# LoginNFC.net
KiCad netlist of a schematic drawn in EAGLE
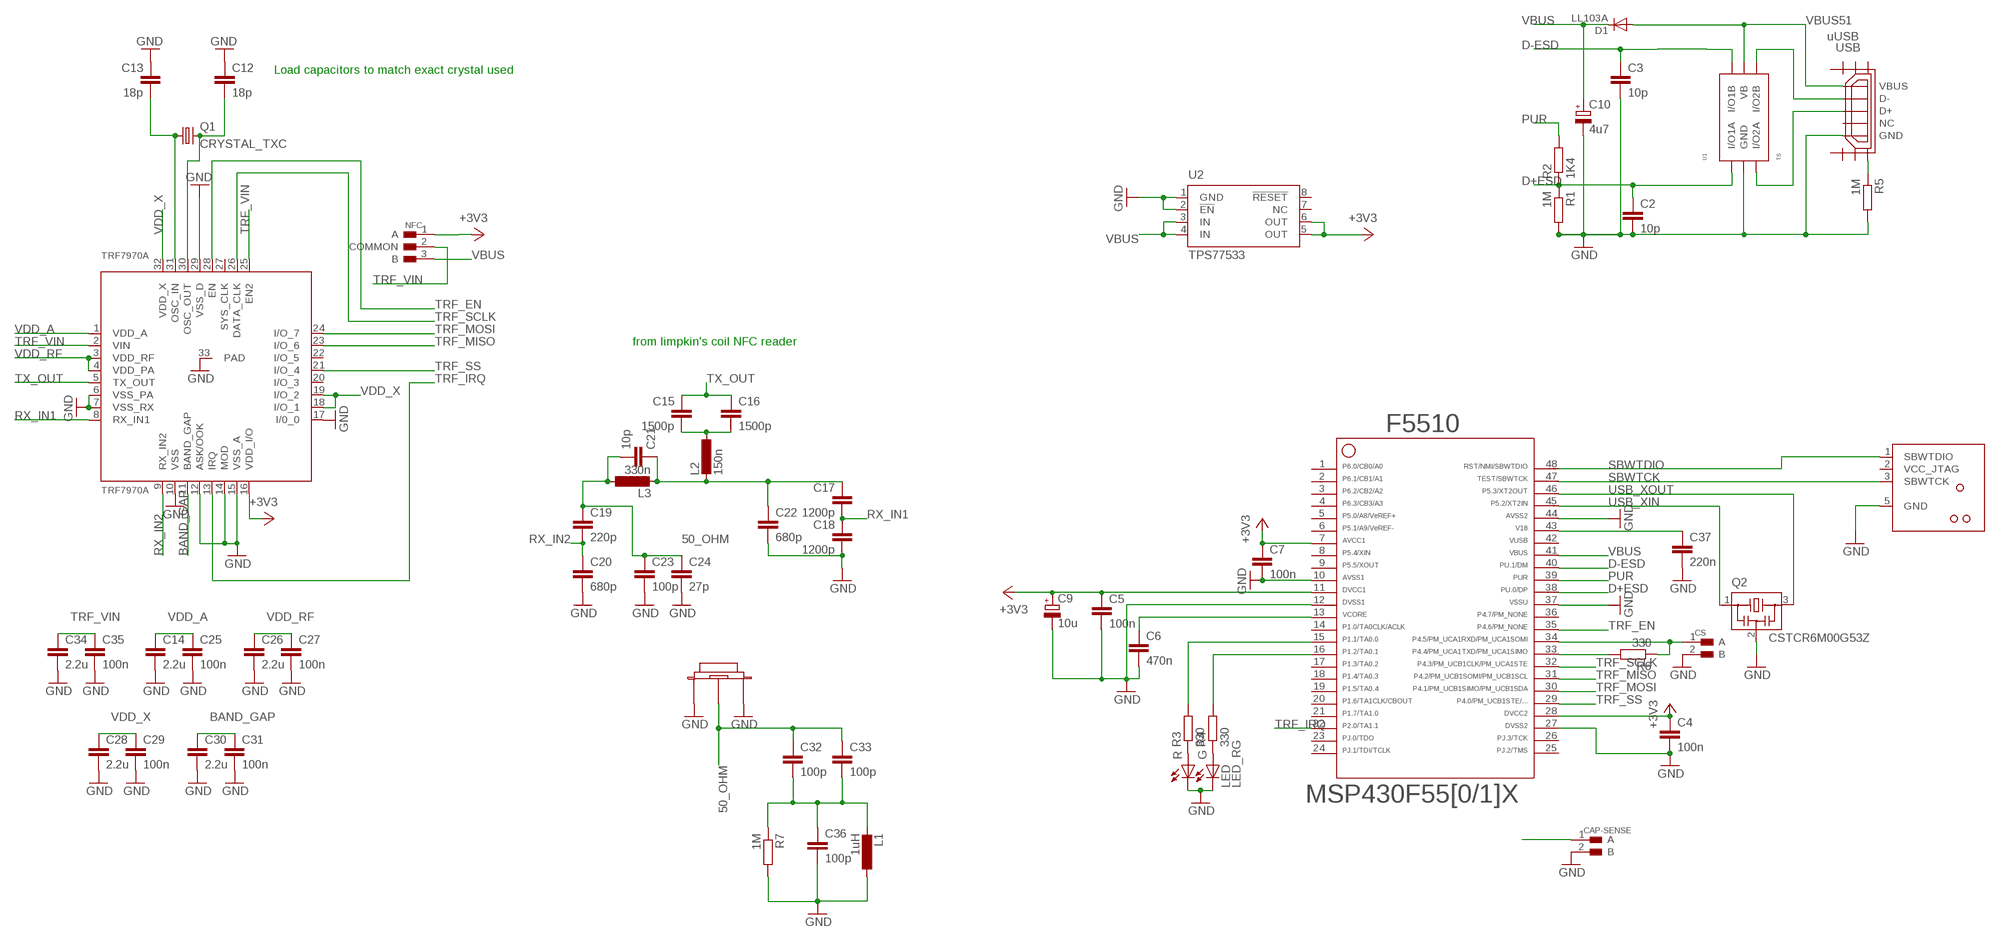
[diagram p0: schematic, sheet 1]

(export (version "E")
  (design (tool "Eeschema 10.0.6"))
  (components
    (comp (ref "C2")
      (value "10p")
      (footprint "eagle-import:C0805")
      (libsource (lib "eagle-import") (part "C-EUC0805"))
    )
    (comp (ref "C3")
      (value "10p")
      (footprint "eagle-import:C0805")
      (libsource (lib "eagle-import") (part "C-EUC0805"))
    )
    (comp (ref "C4")
      (value "100n")
      (footprint "eagle-import:C0805")
      (libsource (lib "eagle-import") (part "C-EUC0805"))
    )
    (comp (ref "C5")
      (value "100n")
      (footprint "eagle-import:C0805")
      (libsource (lib "eagle-import") (part "C-EUC0805"))
    )
    (comp (ref "C6")
      (value "470n")
      (footprint "eagle-import:C0805")
      (libsource (lib "eagle-import") (part "C-EUC0805"))
    )
    (comp (ref "C7")
      (value "100n")
      (footprint "eagle-import:C0805")
      (libsource (lib "eagle-import") (part "C-EUC0805"))
    )
    (comp (ref "C9")
      (value "10u")
      (footprint "eagle-import:A_3216-18R")
      (libsource (lib "eagle-import") (part "CPOL-EUA/3216-18R"))
    )
    (comp (ref "C10")
      (value "4u7")
      (footprint "eagle-import:A_3216-18R")
      (libsource (lib "eagle-import") (part "CPOL-EUA/3216-18R"))
    )
    (comp (ref "C12")
      (value "18p")
      (footprint "eagle-import:C0805")
      (libsource (lib "eagle-import") (part "C-EU_C0805"))
    )
    (comp (ref "C13")
      (value "18p")
      (footprint "eagle-import:C0805")
      (libsource (lib "eagle-import") (part "C-EU_C0805"))
    )
    (comp (ref "C14")
      (value "2.2u")
      (footprint "eagle-import:C0805")
      (libsource (lib "eagle-import") (part "C-EU_C0805"))
    )
    (comp (ref "C15")
      (value "1500p")
      (footprint "eagle-import:C0805")
      (libsource (lib "eagle-import") (part "C-EUC0805"))
    )
    (comp (ref "C16")
      (value "1500p")
      (footprint "eagle-import:C0805")
      (libsource (lib "eagle-import") (part "C-EUC0805"))
    )
    (comp (ref "C17")
      (value "1200p")
      (footprint "eagle-import:C0805")
      (libsource (lib "eagle-import") (part "C-EUC0805"))
    )
    (comp (ref "C18")
      (value "1200p")
      (footprint "eagle-import:C0805")
      (libsource (lib "eagle-import") (part "C-EUC0805"))
    )
    (comp (ref "C19")
      (value "220p")
      (footprint "eagle-import:C0805")
      (libsource (lib "eagle-import") (part "C-EUC0805"))
    )
    (comp (ref "C20")
      (value "680p")
      (footprint "eagle-import:C0805")
      (libsource (lib "eagle-import") (part "C-EUC0805"))
    )
    (comp (ref "C21")
      (value "10p")
      (footprint "eagle-import:C0805")
      (libsource (lib "eagle-import") (part "C-EUC0805"))
    )
    (comp (ref "C22")
      (value "680p")
      (footprint "eagle-import:C0805")
      (libsource (lib "eagle-import") (part "C-EUC0805"))
    )
    (comp (ref "C23")
      (value "100p")
      (footprint "eagle-import:C0805")
      (libsource (lib "eagle-import") (part "C-EUC0805"))
    )
    (comp (ref "C24")
      (value "27p")
      (footprint "eagle-import:C0805")
      (libsource (lib "eagle-import") (part "C-EUC0805"))
    )
    (comp (ref "C25")
      (value "100n")
      (footprint "eagle-import:C0805")
      (libsource (lib "eagle-import") (part "C-EU_C0805"))
    )
    (comp (ref "C26")
      (value "2.2u")
      (footprint "eagle-import:C0805")
      (libsource (lib "eagle-import") (part "C-EU_C0805"))
    )
    (comp (ref "C27")
      (value "100n")
      (footprint "eagle-import:C0805")
      (libsource (lib "eagle-import") (part "C-EU_C0805"))
    )
    (comp (ref "C28")
      (value "2.2u")
      (footprint "eagle-import:C0805")
      (libsource (lib "eagle-import") (part "C-EU_C0805"))
    )
    (comp (ref "C29")
      (value "100n")
      (footprint "eagle-import:C0805")
      (libsource (lib "eagle-import") (part "C-EU_C0805"))
    )
    (comp (ref "C30")
      (value "2.2u")
      (footprint "eagle-import:C0805")
      (libsource (lib "eagle-import") (part "C-EU_C0805"))
    )
    (comp (ref "C31")
      (value "100n")
      (footprint "eagle-import:C0805")
      (libsource (lib "eagle-import") (part "C-EU_C0805"))
    )
    (comp (ref "C32")
      (value "100p")
      (footprint "eagle-import:C0805")
      (libsource (lib "eagle-import") (part "C-EUC0805"))
    )
    (comp (ref "C33")
      (value "100p")
      (footprint "eagle-import:C0805")
      (libsource (lib "eagle-import") (part "C-EUC0805"))
    )
    (comp (ref "C34")
      (value "2.2u")
      (footprint "eagle-import:C0805")
      (libsource (lib "eagle-import") (part "C-EU_C0805"))
    )
    (comp (ref "C35")
      (value "100n")
      (footprint "eagle-import:C0805")
      (libsource (lib "eagle-import") (part "C-EU_C0805"))
    )
    (comp (ref "C36")
      (value "100p")
      (footprint "eagle-import:C0805")
      (libsource (lib "eagle-import") (part "C-EUC0805"))
    )
    (comp (ref "C37")
      (value "220n")
      (footprint "eagle-import:C0805")
      (libsource (lib "eagle-import") (part "C-EUC0805"))
    )
    (comp (ref "CAP-SENSE")
      (value "PAD")
      (footprint "eagle-import:JUMP-2")
      (libsource (lib "eagle-import") (part "PAD"))
    )
    (comp (ref "CS")
      (value "PAD")
      (footprint "eagle-import:JUMP-2")
      (libsource (lib "eagle-import") (part "PAD"))
    )
    (comp (ref "D1")
      (value "LL103A")
      (footprint "eagle-import:SOD-80")
      (libsource (lib "eagle-import") (part "DIODE"))
    )
    (comp (ref "F5510")
      (value "F55[0/1]X---PT48")
      (footprint "eagle-import:PT48")
      (libsource (lib "eagle-import") (part "F55[0/1]X---PT48"))
    )
    (comp (ref "JTAG")
      (value "TC2030-MSP430-NO-UART-NL")
      (footprint "eagle-import:TC2030-MSP430-NL-NO-UART")
      (libsource (lib "eagle-import") (part "TC2030-MSP430-NO-UART-NL"))
    )
    (comp (ref "L1")
      (value "1uH")
      (footprint "eagle-import:RADIAL_MIDMOUNT_5")
      (libsource (lib "eagle-import") (part "L-EU_MIDMOUNT"))
    )
    (comp (ref "L2")
      (value "150n")
      (footprint "eagle-import:L1008")
      (libsource (lib "eagle-import") (part "L-EU_L1008"))
    )
    (comp (ref "L3")
      (value "330n")
      (footprint "eagle-import:L1008")
      (libsource (lib "eagle-import") (part "L-EU_L1008"))
    )
    (comp (ref "LED")
      (value "LED_RG")
      (footprint "eagle-import:1411")
      (libsource (lib "eagle-import") (part "LED_RG"))
    )
    (comp (ref "NFC")
      (value "JUMPER")
      (footprint "eagle-import:SMT-JUMPER")
      (libsource (lib "eagle-import") (part "JUMPER"))
    )
    (comp (ref "Q1")
      (value "CRYSTAL_TXC")
      (footprint "eagle-import:CRYSTAL_TCX")
      (libsource (lib "eagle-import") (part "CRYSTAL_TXC"))
    )
    (comp (ref "Q2")
      (value "CSTCR6M00G53Z")
      (footprint "eagle-import:CSTCR6M")
      (fields (field (name "MPN") "CSTCR6M00G53-R0"))
      (libsource (lib "eagle-import") (part "CSTCR6M00G53Z"))
    )
    (comp (ref "R1")
      (value "1M")
      (footprint "eagle-import:R0805")
      (libsource (lib "eagle-import") (part "R-EU_R0805"))
    )
    (comp (ref "R2")
      (value "1K4")
      (footprint "eagle-import:R0805")
      (libsource (lib "eagle-import") (part "R-EU_R0805"))
    )
    (comp (ref "R3")
      (value "330")
      (footprint "eagle-import:R0805")
      (libsource (lib "eagle-import") (part "R-EU_R0805"))
    )
    (comp (ref "R4")
      (value "330")
      (footprint "eagle-import:R0805")
      (libsource (lib "eagle-import") (part "R-EU_R0805"))
    )
    (comp (ref "R5")
      (value "1M")
      (footprint "eagle-import:R0805")
      (libsource (lib "eagle-import") (part "R-EU_R0805"))
    )
    (comp (ref "R6")
      (value "330")
      (footprint "eagle-import:R0805")
      (libsource (lib "eagle-import") (part "R-EU_R0805"))
    )
    (comp (ref "R7")
      (value "1M")
      (footprint "eagle-import:R0805")
      (libsource (lib "eagle-import") (part "R-EU_R0805"))
    )
    (comp (ref "TRF7970A")
      (value "TRF7970A")
      (footprint "eagle-import:QFN(RHB)32")
      (libsource (lib "eagle-import") (part "TRF7970A"))
    )
    (comp (ref "U1")
      (value "TS")
      (footprint "eagle-import:SOT-457")
      (libsource (lib "eagle-import") (part "IP4234CZ6SOT-457"))
    )
    (comp (ref "U2")
      (value "TPS77533")
      (footprint "eagle-import:SO08")
      (libsource (lib "eagle-import") (part "TPS77533"))
    )
    (comp (ref "UFL1")
      (value "U.FL")
      (footprint "eagle-import:U.FL")
      (libsource (lib "eagle-import") (part "U.FL"))
    )
    (comp (ref "USB")
      (value "uUSB")
      (footprint "eagle-import:HIROSE-ZX62R-B-5P")
      (libsource (lib "eagle-import") (part "USB_MICRO_FLIPPED"))
    )
  )
  (nets
    (net (code "1") (name "+3V3") (class "Default")
      (node (ref "C4") (pin "1") (pinfunction "1_1") (pintype "passive"))
      (node (ref "C5") (pin "1") (pinfunction "1_1") (pintype "passive"))
      (node (ref "C7") (pin "1") (pinfunction "1_1") (pintype "passive"))
      (node (ref "C9") (pin "+") (pinfunction "+_+") (pintype "passive"))
      (node (ref "F5510") (pin "11") (pinfunction "11_11") (pintype "power_in"))
      (node (ref "F5510") (pin "28") (pinfunction "28_28") (pintype "power_in"))
      (node (ref "F5510") (pin "7") (pinfunction "7_7") (pintype "power_in"))
      (node (ref "NFC") (pin "1") (pinfunction "A_1") (pintype "bidirectional"))
      (node (ref "TRF7970A") (pin "16") (pinfunction "VDD_I/O_16") (pintype "power_in"))
      (node (ref "U2") (pin "5") (pinfunction "OUT_5") (pintype "output"))
      (node (ref "U2") (pin "6") (pinfunction "OUT_6") (pintype "output"))
    )
    (net (code "2") (name "/42") (class "Default")
      (node (ref "F5510") (pin "42") (pinfunction "42_42") (pintype "power_in"))
    )
    (net (code "3") (name "/50_OHM") (class "Default")
      (node (ref "C19") (pin "1") (pinfunction "1_1") (pintype "passive"))
      (node (ref "C21") (pin "2") (pinfunction "2_2") (pintype "passive"))
      (node (ref "C23") (pin "1") (pinfunction "1_1") (pintype "passive"))
      (node (ref "C24") (pin "1") (pinfunction "1_1") (pintype "passive"))
      (node (ref "C32") (pin "1") (pinfunction "1_1") (pintype "passive"))
      (node (ref "C33") (pin "1") (pinfunction "1_1") (pintype "passive"))
      (node (ref "L3") (pin "1") (pinfunction "1_1") (pintype "passive"))
      (node (ref "UFL1") (pin "RF") (pinfunction "RF_RF") (pintype "bidirectional"))
    )
    (net (code "4") (name "/BAND_GAP") (class "Default")
      (node (ref "C30") (pin "1") (pinfunction "1_1") (pintype "passive"))
      (node (ref "C31") (pin "1") (pinfunction "1_1") (pintype "passive"))
      (node (ref "TRF7970A") (pin "11") (pinfunction "BAND_GAP_11") (pintype "output"))
    )
    (net (code "5") (name "/D+ESD") (class "Default")
      (node (ref "C2") (pin "1") (pinfunction "1_1") (pintype "passive"))
      (node (ref "F5510") (pin "38") (pinfunction "38_38") (pintype "bidirectional"))
      (node (ref "R1") (pin "1") (pinfunction "1_1") (pintype "passive"))
      (node (ref "R2") (pin "1") (pinfunction "1_1") (pintype "passive"))
      (node (ref "U1") (pin "1") (pinfunction "I/O1A_1") (pintype "bidirectional"))
    )
    (net (code "6") (name "/D-ESD") (class "Default")
      (node (ref "C3") (pin "1") (pinfunction "1_1") (pintype "passive"))
      (node (ref "F5510") (pin "40") (pinfunction "40_40") (pintype "bidirectional"))
      (node (ref "U1") (pin "6") (pinfunction "I/O1B_6") (pintype "bidirectional"))
    )
    (net (code "7") (name "/PUR") (class "Default")
      (node (ref "F5510") (pin "39") (pinfunction "39_39") (pintype "bidirectional"))
      (node (ref "R2") (pin "2") (pinfunction "2_2") (pintype "passive"))
    )
    (net (code "8") (name "/RX_IN1") (class "Default")
      (node (ref "C17") (pin "2") (pinfunction "2_2") (pintype "passive"))
      (node (ref "C18") (pin "1") (pinfunction "1_1") (pintype "passive"))
      (node (ref "TRF7970A") (pin "8") (pinfunction "RX_IN1_8") (pintype "input"))
    )
    (net (code "9") (name "/RX_IN2") (class "Default")
      (node (ref "C19") (pin "2") (pinfunction "2_2") (pintype "passive"))
      (node (ref "C20") (pin "1") (pinfunction "1_1") (pintype "passive"))
      (node (ref "TRF7970A") (pin "9") (pinfunction "RX_IN2_9") (pintype "input"))
    )
    (net (code "10") (name "/SBWTCK") (class "Default")
      (node (ref "F5510") (pin "47") (pinfunction "47_47") (pintype "input"))
      (node (ref "JTAG") (pin "3") (pinfunction "SBWTCK_3") (pintype "bidirectional"))
    )
    (net (code "11") (name "/SBWTDIO") (class "Default")
      (node (ref "F5510") (pin "48") (pinfunction "48_48") (pintype "bidirectional"))
      (node (ref "JTAG") (pin "1") (pinfunction "SBWTDIO_1") (pintype "bidirectional"))
    )
    (net (code "12") (name "/TRF_EN") (class "Default")
      (node (ref "F5510") (pin "35") (pinfunction "35_35") (pintype "bidirectional"))
      (node (ref "TRF7970A") (pin "28") (pinfunction "EN_28") (pintype "input"))
    )
    (net (code "13") (name "/TRF_IRQ") (class "Default")
      (node (ref "F5510") (pin "22") (pinfunction "22_22") (pintype "bidirectional"))
      (node (ref "TRF7970A") (pin "13") (pinfunction "IRQ_13") (pintype "output"))
    )
    (net (code "14") (name "/TRF_MISO") (class "Default")
      (node (ref "F5510") (pin "31") (pinfunction "31_31") (pintype "bidirectional"))
      (node (ref "TRF7970A") (pin "23") (pinfunction "I/O_6_23") (pintype "bidirectional"))
    )
    (net (code "15") (name "/TRF_MOSI") (class "Default")
      (node (ref "F5510") (pin "30") (pinfunction "30_30") (pintype "bidirectional"))
      (node (ref "TRF7970A") (pin "24") (pinfunction "I/O_7_24") (pintype "bidirectional"))
    )
    (net (code "16") (name "/TRF_SCLK") (class "Default")
      (node (ref "F5510") (pin "32") (pinfunction "32_32") (pintype "bidirectional"))
      (node (ref "TRF7970A") (pin "26") (pinfunction "DATA_CLK_26") (pintype "input"))
    )
    (net (code "17") (name "/TRF_SS") (class "Default")
      (node (ref "F5510") (pin "29") (pinfunction "29_29") (pintype "bidirectional"))
      (node (ref "TRF7970A") (pin "21") (pinfunction "I/O_4_21") (pintype "bidirectional"))
    )
    (net (code "18") (name "/TRF_VIN") (class "Default")
      (node (ref "C34") (pin "1") (pinfunction "1_1") (pintype "passive"))
      (node (ref "C35") (pin "1") (pinfunction "1_1") (pintype "passive"))
      (node (ref "NFC") (pin "2") (pinfunction "COMMON_2") (pintype "bidirectional"))
      (node (ref "TRF7970A") (pin "2") (pinfunction "VIN_2") (pintype "power_in"))
      (node (ref "TRF7970A") (pin "25") (pinfunction "EN2_25") (pintype "input"))
    )
    (net (code "19") (name "/TX_OUT") (class "Default")
      (node (ref "C15") (pin "1") (pinfunction "1_1") (pintype "passive"))
      (node (ref "C16") (pin "1") (pinfunction "1_1") (pintype "passive"))
      (node (ref "TRF7970A") (pin "5") (pinfunction "TX_OUT_5") (pintype "output"))
    )
    (net (code "20") (name "/USB_XIN") (class "Default")
      (node (ref "F5510") (pin "45") (pinfunction "45_45") (pintype "bidirectional"))
      (node (ref "Q2") (pin "1") (pinfunction "1_1") (pintype "passive"))
    )
    (net (code "21") (name "/USB_XOUT") (class "Default")
      (node (ref "F5510") (pin "46") (pinfunction "46_46") (pintype "power_in"))
      (node (ref "Q2") (pin "3") (pinfunction "3_3") (pintype "passive"))
    )
    (net (code "22") (name "/VBUS") (class "Default")
      (node (ref "C10") (pin "+") (pinfunction "+_+") (pintype "passive"))
      (node (ref "D1") (pin "2") (pinfunction "K_2") (pintype "passive"))
      (node (ref "F5510") (pin "41") (pinfunction "41_41") (pintype "power_in"))
      (node (ref "NFC") (pin "3") (pinfunction "B_3") (pintype "bidirectional"))
      (node (ref "U2") (pin "3") (pinfunction "IN_3") (pintype "input"))
      (node (ref "U2") (pin "4") (pinfunction "IN_4") (pintype "input"))
    )
    (net (code "23") (name "/VBUS51") (class "Default")
      (node (ref "D1") (pin "1") (pinfunction "A_1") (pintype "passive"))
      (node (ref "U1") (pin "5") (pinfunction "VB_5") (pintype "bidirectional"))
      (node (ref "USB") (pin "VBUS") (pinfunction "VBUS_VBUS") (pintype "input"))
    )
    (net (code "24") (name "/VCC_JTAG") (class "Default")
      (node (ref "JTAG") (pin "2") (pinfunction "VCC_JTAG_2") (pintype "power_in"))
    )
    (net (code "25") (name "/VDD_A") (class "Default")
      (node (ref "C14") (pin "1") (pinfunction "1_1") (pintype "passive"))
      (node (ref "C25") (pin "1") (pinfunction "1_1") (pintype "passive"))
      (node (ref "TRF7970A") (pin "1") (pinfunction "VDD_A_1") (pintype "power_in"))
    )
    (net (code "26") (name "/VDD_RF") (class "Default")
      (node (ref "C26") (pin "1") (pinfunction "1_1") (pintype "passive"))
      (node (ref "C27") (pin "1") (pinfunction "1_1") (pintype "passive"))
      (node (ref "TRF7970A") (pin "3") (pinfunction "VDD_RF_3") (pintype "power_in"))
      (node (ref "TRF7970A") (pin "4") (pinfunction "VDD_PA_4") (pintype "power_in"))
    )
    (net (code "27") (name "/VDD_X") (class "Default")
      (node (ref "C28") (pin "1") (pinfunction "1_1") (pintype "passive"))
      (node (ref "C29") (pin "1") (pinfunction "1_1") (pintype "passive"))
      (node (ref "TRF7970A") (pin "18") (pinfunction "I/O_1_18") (pintype "bidirectional"))
      (node (ref "TRF7970A") (pin "19") (pinfunction "I/O_2_19") (pintype "bidirectional"))
      (node (ref "TRF7970A") (pin "32") (pinfunction "VDD_X_32") (pintype "power_in"))
    )
    (net (code "28") (name "GND") (class "Default")
      (node (ref "C10") (pin "-") (pinfunction "-_-") (pintype "passive"))
      (node (ref "C12") (pin "1") (pinfunction "1_1") (pintype "passive"))
      (node (ref "C13") (pin "1") (pinfunction "1_1") (pintype "passive"))
      (node (ref "C14") (pin "2") (pinfunction "2_2") (pintype "passive"))
      (node (ref "C18") (pin "2") (pinfunction "2_2") (pintype "passive"))
      (node (ref "C2") (pin "2") (pinfunction "2_2") (pintype "passive"))
      (node (ref "C20") (pin "2") (pinfunction "2_2") (pintype "passive"))
      (node (ref "C22") (pin "2") (pinfunction "2_2") (pintype "passive"))
      (node (ref "C23") (pin "2") (pinfunction "2_2") (pintype "passive"))
      (node (ref "C24") (pin "2") (pinfunction "2_2") (pintype "passive"))
      (node (ref "C25") (pin "2") (pinfunction "2_2") (pintype "passive"))
      (node (ref "C26") (pin "2") (pinfunction "2_2") (pintype "passive"))
      (node (ref "C27") (pin "2") (pinfunction "2_2") (pintype "passive"))
      (node (ref "C28") (pin "2") (pinfunction "2_2") (pintype "passive"))
      (node (ref "C29") (pin "2") (pinfunction "2_2") (pintype "passive"))
      (node (ref "C3") (pin "2") (pinfunction "2_2") (pintype "passive"))
      (node (ref "C30") (pin "2") (pinfunction "2_2") (pintype "passive"))
      (node (ref "C31") (pin "2") (pinfunction "2_2") (pintype "passive"))
      (node (ref "C34") (pin "2") (pinfunction "2_2") (pintype "passive"))
      (node (ref "C35") (pin "2") (pinfunction "2_2") (pintype "passive"))
      (node (ref "C36") (pin "2") (pinfunction "2_2") (pintype "passive"))
      (node (ref "C37") (pin "2") (pinfunction "2_2") (pintype "passive"))
      (node (ref "C4") (pin "2") (pinfunction "2_2") (pintype "passive"))
      (node (ref "C5") (pin "2") (pinfunction "2_2") (pintype "passive"))
      (node (ref "C6") (pin "2") (pinfunction "2_2") (pintype "passive"))
      (node (ref "C7") (pin "2") (pinfunction "2_2") (pintype "passive"))
      (node (ref "C9") (pin "-") (pinfunction "-_-") (pintype "passive"))
      (node (ref "CAP-SENSE") (pin "2") (pinfunction "B_2") (pintype "bidirectional"))
      (node (ref "CS") (pin "2") (pinfunction "B_2") (pintype "bidirectional"))
      (node (ref "F5510") (pin "10") (pinfunction "10_10") (pintype "power_in"))
      (node (ref "F5510") (pin "12") (pinfunction "12_12") (pintype "power_in"))
      (node (ref "F5510") (pin "27") (pinfunction "27_27") (pintype "power_in"))
      (node (ref "F5510") (pin "37") (pinfunction "37_37") (pintype "power_in"))
      (node (ref "F5510") (pin "44") (pinfunction "44_44") (pintype "power_in"))
      (node (ref "JTAG") (pin "5") (pinfunction "GND_5") (pintype "power_in"))
      (node (ref "L1") (pin "P$1") (pinfunction "1_P$1") (pintype "passive"))
      (node (ref "LED") (pin "P$3") (pinfunction "RED_C_P$3") (pintype "passive"))
      (node (ref "LED") (pin "P$4") (pinfunction "GREEN_C_P$4") (pintype "passive"))
      (node (ref "Q2") (pin "2") (pinfunction "2_2") (pintype "passive"))
      (node (ref "R1") (pin "2") (pinfunction "2_2") (pintype "passive"))
      (node (ref "R5") (pin "2") (pinfunction "2_2") (pintype "passive"))
      (node (ref "R7") (pin "2") (pinfunction "2_2") (pintype "passive"))
      (node (ref "TRF7970A") (pin "10") (pinfunction "VSS_10") (pintype "power_in"))
      (node (ref "TRF7970A") (pin "12") (pinfunction "ASK/OOK_12") (pintype "bidirectional"))
      (node (ref "TRF7970A") (pin "14") (pinfunction "MOD_14") (pintype "input"))
      (node (ref "TRF7970A") (pin "15") (pinfunction "VSS_A_15") (pintype "power_in"))
      (node (ref "TRF7970A") (pin "17") (pinfunction "I/0_0_17") (pintype "bidirectional"))
      (node (ref "TRF7970A") (pin "29") (pinfunction "VSS_D_29") (pintype "power_in"))
      (node (ref "TRF7970A") (pin "33") (pinfunction "PAD_33") (pintype "power_in"))
      (node (ref "TRF7970A") (pin "6") (pinfunction "VSS_PA_6") (pintype "power_in"))
      (node (ref "TRF7970A") (pin "7") (pinfunction "VSS_RX_7") (pintype "power_in"))
      (node (ref "U1") (pin "2") (pinfunction "GND_2") (pintype "bidirectional"))
      (node (ref "U2") (pin "1") (pinfunction "GND_1") (pintype "power_in"))
      (node (ref "U2") (pin "2") (pinfunction "~{EN}_2") (pintype "input"))
      (node (ref "UFL1") (pin "GND1") (pinfunction "GND1_GND1") (pintype "bidirectional"))
      (node (ref "UFL1") (pin "GND2") (pinfunction "GND2_GND2") (pintype "bidirectional"))
      (node (ref "USB") (pin "GND") (pinfunction "GND_GND") (pintype "input"))
    )
    (net (code "29") (name "Net-(C6-Pad1)") (class "Default")
      (node (ref "C6") (pin "1") (pinfunction "1_1") (pintype "passive"))
      (node (ref "F5510") (pin "13") (pinfunction "13_13") (pintype "power_in"))
    )
    (net (code "30") (name "Net-(C15-Pad2)") (class "Default")
      (node (ref "C15") (pin "2") (pinfunction "2_2") (pintype "passive"))
      (node (ref "C16") (pin "2") (pinfunction "2_2") (pintype "passive"))
      (node (ref "L2") (pin "1") (pinfunction "1_1") (pintype "passive"))
    )
    (net (code "31") (name "Net-(C17-Pad1)") (class "Default")
      (node (ref "C17") (pin "1") (pinfunction "1_1") (pintype "passive"))
      (node (ref "C21") (pin "1") (pinfunction "1_1") (pintype "passive"))
      (node (ref "C22") (pin "1") (pinfunction "1_1") (pintype "passive"))
      (node (ref "L2") (pin "2") (pinfunction "2_2") (pintype "passive"))
      (node (ref "L3") (pin "2") (pinfunction "2_2") (pintype "passive"))
    )
    (net (code "32") (name "Net-(C37-Pad1)") (class "Default")
      (node (ref "C37") (pin "1") (pinfunction "1_1") (pintype "passive"))
      (node (ref "F5510") (pin "43") (pinfunction "43_43") (pintype "power_in"))
    )
    (net (code "33") (name "Net-(CS-A)") (class "Default")
      (node (ref "CS") (pin "1") (pinfunction "A_1") (pintype "bidirectional"))
      (node (ref "F5510") (pin "34") (pinfunction "34_34") (pintype "bidirectional"))
      (node (ref "R6") (pin "1") (pinfunction "1_1") (pintype "passive"))
    )
    (net (code "34") (name "Net-(F5510-Pad15)") (class "Default")
      (node (ref "F5510") (pin "15") (pinfunction "15_15") (pintype "bidirectional"))
      (node (ref "R3") (pin "2") (pinfunction "2_2") (pintype "passive"))
    )
    (net (code "35") (name "Net-(F5510-Pad16)") (class "Default")
      (node (ref "F5510") (pin "16") (pinfunction "16_16") (pintype "bidirectional"))
      (node (ref "R4") (pin "2") (pinfunction "2_2") (pintype "passive"))
    )
    (net (code "36") (name "Net-(F5510-Pad33)") (class "Default")
      (node (ref "F5510") (pin "33") (pinfunction "33_33") (pintype "bidirectional"))
      (node (ref "R6") (pin "2") (pinfunction "2_2") (pintype "passive"))
    )
    (net (code "37") (name "Net-(L1-2)") (class "Default")
      (node (ref "C32") (pin "2") (pinfunction "2_2") (pintype "passive"))
      (node (ref "C33") (pin "2") (pinfunction "2_2") (pintype "passive"))
      (node (ref "C36") (pin "1") (pinfunction "1_1") (pintype "passive"))
      (node (ref "L1") (pin "P$2") (pinfunction "2_P$2") (pintype "passive"))
      (node (ref "R7") (pin "1") (pinfunction "1_1") (pintype "passive"))
    )
    (net (code "38") (name "Net-(LED-GREEN_A)") (class "Default")
      (node (ref "LED") (pin "P$2") (pinfunction "GREEN_A_P$2") (pintype "passive"))
      (node (ref "R4") (pin "1") (pinfunction "1_1") (pintype "passive"))
    )
    (net (code "39") (name "Net-(LED-RED_A)") (class "Default")
      (node (ref "LED") (pin "P$1") (pinfunction "RED_A_P$1") (pintype "passive"))
      (node (ref "R3") (pin "1") (pinfunction "1_1") (pintype "passive"))
    )
    (net (code "40") (name "Net-(R5-Pad1)") (class "Default")
      (node (ref "R5") (pin "1") (pinfunction "1_1") (pintype "passive"))
      (node (ref "USB") (pin "SHIELD3") (pinfunction "SHIELD3_SHIELD3") (pintype "bidirectional"))
    )
    (net (code "41") (name "Net-(TRF7970A-OSC_IN)") (class "Default")
      (node (ref "C13") (pin "2") (pinfunction "2_2") (pintype "passive"))
      (node (ref "Q1") (pin "1") (pinfunction "1_1") (pintype "passive"))
      (node (ref "TRF7970A") (pin "31") (pinfunction "OSC_IN_31") (pintype "input"))
    )
    (net (code "42") (name "Net-(TRF7970A-OSC_OUT)") (class "Default")
      (node (ref "C12") (pin "2") (pinfunction "2_2") (pintype "passive"))
      (node (ref "Q1") (pin "2") (pinfunction "2_2") (pintype "passive"))
      (node (ref "TRF7970A") (pin "30") (pinfunction "OSC_OUT_30") (pintype "output"))
    )
    (net (code "43") (name "Net-(U1-I{slash}O2A)") (class "Default")
      (node (ref "U1") (pin "3") (pinfunction "I/O2A_3") (pintype "bidirectional"))
      (node (ref "USB") (pin "D+") (pinfunction "D+_D+") (pintype "input"))
    )
    (net (code "44") (name "Net-(U1-I{slash}O2B)") (class "Default")
      (node (ref "U1") (pin "4") (pinfunction "I/O2B_4") (pintype "bidirectional"))
      (node (ref "USB") (pin "D-") (pinfunction "D-_D-") (pintype "input"))
    )
    (net (code "45") (name "unconnected-(CAP-SENSE-A-Pad1)") (class "Default")
      (node (ref "CAP-SENSE") (pin "1") (pinfunction "A_1") (pintype "bidirectional"))
    )
    (net (code "46") (name "unconnected-(F5510-Pad1)") (class "Default")
      (node (ref "F5510") (pin "1") (pinfunction "1_1") (pintype "bidirectional"))
    )
    (net (code "47") (name "unconnected-(F5510-Pad2)") (class "Default")
      (node (ref "F5510") (pin "2") (pinfunction "2_2") (pintype "bidirectional"))
    )
    (net (code "48") (name "unconnected-(F5510-Pad3)") (class "Default")
      (node (ref "F5510") (pin "3") (pinfunction "3_3") (pintype "bidirectional"))
    )
    (net (code "49") (name "unconnected-(F5510-Pad4)") (class "Default")
      (node (ref "F5510") (pin "4") (pinfunction "4_4") (pintype "bidirectional"))
    )
    (net (code "50") (name "unconnected-(F5510-Pad5)") (class "Default")
      (node (ref "F5510") (pin "5") (pinfunction "5_5") (pintype "bidirectional"))
    )
    (net (code "51") (name "unconnected-(F5510-Pad6)") (class "Default")
      (node (ref "F5510") (pin "6") (pinfunction "6_6") (pintype "bidirectional"))
    )
    (net (code "52") (name "unconnected-(F5510-Pad8)") (class "Default")
      (node (ref "F5510") (pin "8") (pinfunction "8_8") (pintype "bidirectional"))
    )
    (net (code "53") (name "unconnected-(F5510-Pad9)") (class "Default")
      (node (ref "F5510") (pin "9") (pinfunction "9_9") (pintype "bidirectional"))
    )
    (net (code "54") (name "unconnected-(F5510-Pad14)") (class "Default")
      (node (ref "F5510") (pin "14") (pinfunction "14_14") (pintype "bidirectional"))
    )
    (net (code "55") (name "unconnected-(F5510-Pad17)") (class "Default")
      (node (ref "F5510") (pin "17") (pinfunction "17_17") (pintype "bidirectional"))
    )
    (net (code "56") (name "unconnected-(F5510-Pad18)") (class "Default")
      (node (ref "F5510") (pin "18") (pinfunction "18_18") (pintype "bidirectional"))
    )
    (net (code "57") (name "unconnected-(F5510-Pad19)") (class "Default")
      (node (ref "F5510") (pin "19") (pinfunction "19_19") (pintype "bidirectional"))
    )
    (net (code "58") (name "unconnected-(F5510-Pad20)") (class "Default")
      (node (ref "F5510") (pin "20") (pinfunction "20_20") (pintype "bidirectional"))
    )
    (net (code "59") (name "unconnected-(F5510-Pad21)") (class "Default")
      (node (ref "F5510") (pin "21") (pinfunction "21_21") (pintype "bidirectional"))
    )
    (net (code "60") (name "unconnected-(F5510-Pad23)") (class "Default")
      (node (ref "F5510") (pin "23") (pinfunction "23_23") (pintype "bidirectional"))
    )
    (net (code "61") (name "unconnected-(F5510-Pad24)") (class "Default")
      (node (ref "F5510") (pin "24") (pinfunction "24_24") (pintype "bidirectional"))
    )
    (net (code "62") (name "unconnected-(F5510-Pad25)") (class "Default")
      (node (ref "F5510") (pin "25") (pinfunction "25_25") (pintype "bidirectional"))
    )
    (net (code "63") (name "unconnected-(F5510-Pad26)") (class "Default")
      (node (ref "F5510") (pin "26") (pinfunction "26_26") (pintype "bidirectional"))
    )
    (net (code "64") (name "unconnected-(F5510-Pad36)") (class "Default")
      (node (ref "F5510") (pin "36") (pinfunction "36_36") (pintype "bidirectional"))
    )
    (net (code "65") (name "unconnected-(TRF7970A-I{slash}O_3-Pad20)") (class "Default")
      (node (ref "TRF7970A") (pin "20") (pinfunction "I/O_3_20") (pintype "bidirectional"))
    )
    (net (code "66") (name "unconnected-(TRF7970A-I{slash}O_5-Pad22)") (class "Default")
      (node (ref "TRF7970A") (pin "22") (pinfunction "I/O_5_22") (pintype "bidirectional"))
    )
    (net (code "67") (name "unconnected-(TRF7970A-SYS_CLK-Pad27)") (class "Default")
      (node (ref "TRF7970A") (pin "27") (pinfunction "SYS_CLK_27") (pintype "output"))
    )
    (net (code "68") (name "unconnected-(U2-NC-Pad7)") (class "Default")
      (node (ref "U2") (pin "7") (pinfunction "NC_7") (pintype "output"))
    )
    (net (code "69") (name "unconnected-(U2-~{RESET}-Pad8)") (class "Default")
      (node (ref "U2") (pin "8") (pinfunction "~{RESET}_8") (pintype "output"))
    )
    (net (code "70") (name "unconnected-(USB-PadNC)") (class "Default")
      (node (ref "USB") (pin "NC") (pinfunction "NC_NC") (pintype "no_connect"))
    )
    (net (code "71") (name "unconnected-(USB-PadSHIELD1)") (class "Default")
      (node (ref "USB") (pin "SHIELD1") (pinfunction "SHIELD1_SHIELD1") (pintype "bidirectional"))
    )
    (net (code "72") (name "unconnected-(USB-PadSHIELD2)") (class "Default")
      (node (ref "USB") (pin "SHIELD2") (pinfunction "SHIELD2_SHIELD2") (pintype "bidirectional"))
    )
    (net (code "73") (name "unconnected-(USB-PadSHIELD4)") (class "Default")
      (node (ref "USB") (pin "SHIELD4") (pinfunction "SHIELD4_SHIELD4") (pintype "bidirectional"))
    )
    (net (code "74") (name "unconnected-(USB-PadSHIELD5)") (class "Default")
      (node (ref "USB") (pin "SHIELD5") (pinfunction "SHIELD5_SHIELD5") (pintype "bidirectional"))
    )
    (net (code "75") (name "unconnected-(USB-PadSHIELD6)") (class "Default")
      (node (ref "USB") (pin "SHIELD6") (pinfunction "SHIELD6_SHIELD6") (pintype "bidirectional"))
    )
  )
)
